# v1.net
KiCad netlist of a schematic drawn in EAGLE
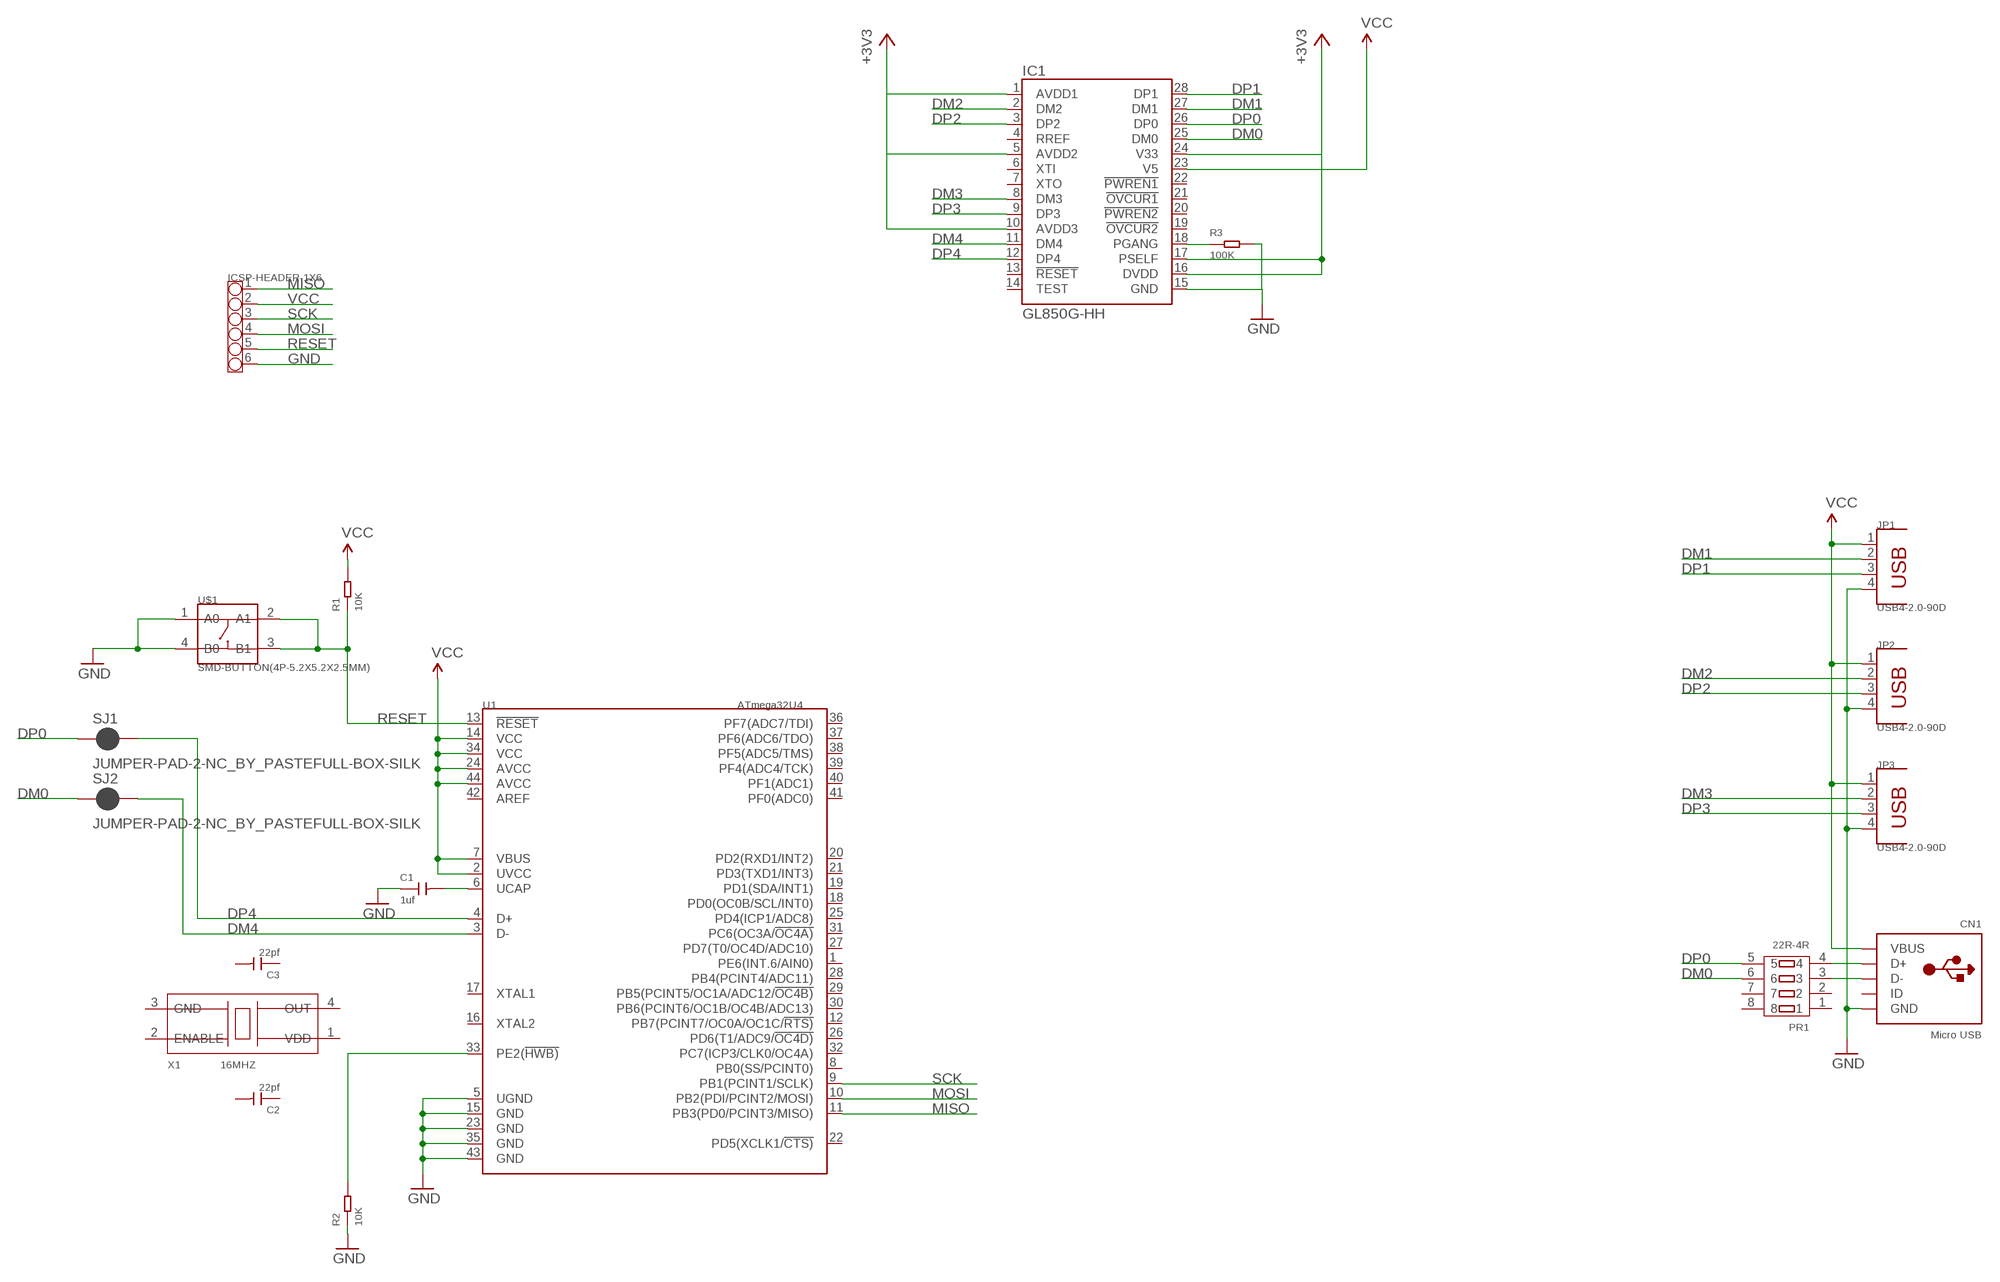
[diagram p0: schematic, sheet 1]

(export (version "E")
  (design (tool "Eeschema 10.0.6"))
  (components
    (comp (ref "C1")
      (value "1uf")
      (footprint "eagle-import:C0603")
      (fields (field (name "MPN") "CC0603KRX7R8BB105"))
      (libsource (lib "eagle-import") (part "CERAMIC-1UF-25V-10%-X7R(0603)"))
    )
    (comp (ref "C2")
      (value "22pf")
      (footprint "eagle-import:C0402")
      (fields (field (name "MPN") "CC0402JRNPO9BN220"))
      (libsource (lib "eagle-import") (part "CERAMIC-22PF-50V-5%-NPO(0402)"))
    )
    (comp (ref "C3")
      (value "22pf")
      (footprint "eagle-import:C0402")
      (fields (field (name "MPN") "CC0402JRNPO9BN220"))
      (libsource (lib "eagle-import") (part "CERAMIC-22PF-50V-5%-NPO(0402)"))
    )
    (comp (ref "CN1")
      (value "Micro USB")
      (footprint "eagle-import:USB-MINIB")
      (libsource (lib "eagle-import") (part "USBMINIB"))
    )
    (comp (ref "IC1")
      (value "GL850G-HH")
      (footprint "eagle-import:SSOP28")
      (libsource (lib "eagle-import") (part "GL850G-HH"))
    )
    (comp (ref "ICSP-HEADER-1X6")
      (value "CONNECTOR-HEADER-6P-3460650P1")
      (footprint "eagle-import:1X6P-2.54-2.54-11.6-3.0-BLACK-MALE")
      (libsource (lib "eagle-import") (part "CONNECTOR-HEADER-6P-3460650P1"))
    )
    (comp (ref "JP1")
      (value "USB4-2.0-90D")
      (footprint "eagle-import:USB4+2P-2.0-90D")
      (libsource (lib "eagle-import") (part "DIP-USB-A-TYPE-FMAL(4+2P-2.0-90D)"))
    )
    (comp (ref "JP2")
      (value "USB4-2.0-90D")
      (footprint "eagle-import:USB4+2P-2.0-90D")
      (libsource (lib "eagle-import") (part "DIP-USB-A-TYPE-FMAL(4+2P-2.0-90D)"))
    )
    (comp (ref "JP3")
      (value "USB4-2.0-90D")
      (footprint "eagle-import:USB4+2P-2.0-90D")
      (libsource (lib "eagle-import") (part "DIP-USB-A-TYPE-FMAL(4+2P-2.0-90D)"))
    )
    (comp (ref "PR1")
      (value "22R-4R")
      (footprint "eagle-import:RA1206-8")
      (fields (field (name "MPN") "YC324-JK-0722RL"))
      (libsource (lib "eagle-import") (part "SMD-RES-ARRAY-22R-4R(1206-8)"))
    )
    (comp (ref "R1")
      (value "10K")
      (footprint "eagle-import:R0603")
      (fields (field (name "MPN") "RC0603FR-0710KL"))
      (libsource (lib "eagle-import") (part "SMD-RES-10K-1%-1/10W(0603)"))
    )
    (comp (ref "R2")
      (value "10K")
      (footprint "eagle-import:R0603")
      (fields (field (name "MPN") "RC0603FR-0710KL"))
      (libsource (lib "eagle-import") (part "SMD-RES-10K-1%-1/10W(0603)"))
    )
    (comp (ref "R3")
      (value "100K")
      (footprint "eagle-import:R0805")
      (fields (field (name "MPN") "RC0805FR-07100KL"))
      (libsource (lib "eagle-import") (part "SMD-RES-100K-1%-1/8W(0805)"))
    )
    (comp (ref "SJ1")
      (value "JUMPER-PAD-2-NC_BY_PASTEFULL-BOX-SILK")
      (footprint "eagle-import:PAD-JUMPER-2-NC_BY_PASTE_YES_SILK_FULL_BOX")
      (libsource (lib "eagle-import") (part "JUMPER-PAD-2-NC_BY_PASTEFULL-BOX-SILK"))
    )
    (comp (ref "SJ2")
      (value "JUMPER-PAD-2-NC_BY_PASTEFULL-BOX-SILK")
      (footprint "eagle-import:PAD-JUMPER-2-NC_BY_PASTE_YES_SILK_FULL_BOX")
      (libsource (lib "eagle-import") (part "JUMPER-PAD-2-NC_BY_PASTEFULL-BOX-SILK"))
    )
    (comp (ref "U$1")
      (value "SMD-BUTTON(4P-5.2X5.2X2.5MM)")
      (footprint "eagle-import:SW4-SMD-5.2X5.2X2.5MM")
      (libsource (lib "eagle-import") (part "SMD-BUTTON(4P-5.2X5.2X2.5MM)"))
    )
    (comp (ref "U1")
      (value "ATmega32U4")
      (footprint "eagle-import:TQFP-44")
      (libsource (lib "eagle-import") (part "MCU-ATMEGA32U4-310010010"))
    )
    (comp (ref "X1")
      (value "16MHZ")
      (footprint "eagle-import:X4-SMD-3.2X2.5X0.7MM")
      (libsource (lib "eagle-import") (part "SMD-CRYSTAL-16MHZ-9PF-10PPM-60R(4P-3.2X2.5MM)"))
    )
  )
  (nets
    (net (code "1") (name "+3V3") (class "Default")
      (node (ref "IC1") (pin "1") (pinfunction "AVDD1_1") (pintype "power_in"))
      (node (ref "IC1") (pin "10") (pinfunction "AVDD3_10") (pintype "power_in"))
      (node (ref "IC1") (pin "16") (pinfunction "DVDD_16") (pintype "power_in"))
      (node (ref "IC1") (pin "17") (pinfunction "PSELF_17") (pintype "input"))
      (node (ref "IC1") (pin "24") (pinfunction "V33_24") (pintype "output"))
      (node (ref "IC1") (pin "5") (pinfunction "AVDD2_5") (pintype "power_in"))
    )
    (net (code "2") (name "/DM0") (class "Default")
      (node (ref "IC1") (pin "25") (pinfunction "DM0_25") (pintype "bidirectional"))
      (node (ref "PR1") (pin "6") (pinfunction "6_6") (pintype "bidirectional"))
      (node (ref "SJ2") (pin "1") (pinfunction "1_1") (pintype "passive"))
    )
    (net (code "3") (name "/DM1") (class "Default")
      (node (ref "IC1") (pin "27") (pinfunction "DM1_27") (pintype "bidirectional"))
      (node (ref "JP1") (pin "2") (pinfunction "2_2") (pintype "bidirectional"))
    )
    (net (code "4") (name "/DM2") (class "Default")
      (node (ref "IC1") (pin "2") (pinfunction "DM2_2") (pintype "bidirectional"))
      (node (ref "JP2") (pin "2") (pinfunction "2_2") (pintype "bidirectional"))
    )
    (net (code "5") (name "/DM3") (class "Default")
      (node (ref "IC1") (pin "8") (pinfunction "DM3_8") (pintype "bidirectional"))
      (node (ref "JP3") (pin "2") (pinfunction "2_2") (pintype "bidirectional"))
    )
    (net (code "6") (name "/DM4") (class "Default")
      (node (ref "IC1") (pin "11") (pinfunction "DM4_11") (pintype "bidirectional"))
      (node (ref "SJ2") (pin "2") (pinfunction "2_2") (pintype "passive"))
      (node (ref "U1") (pin "3") (pinfunction "D-_3") (pintype "bidirectional"))
    )
    (net (code "7") (name "/DP0") (class "Default")
      (node (ref "IC1") (pin "26") (pinfunction "DP0_26") (pintype "bidirectional"))
      (node (ref "PR1") (pin "5") (pinfunction "5_5") (pintype "bidirectional"))
      (node (ref "SJ1") (pin "1") (pinfunction "1_1") (pintype "passive"))
    )
    (net (code "8") (name "/DP1") (class "Default")
      (node (ref "IC1") (pin "28") (pinfunction "DP1_28") (pintype "bidirectional"))
      (node (ref "JP1") (pin "3") (pinfunction "3_3") (pintype "bidirectional"))
    )
    (net (code "9") (name "/DP2") (class "Default")
      (node (ref "IC1") (pin "3") (pinfunction "DP2_3") (pintype "bidirectional"))
      (node (ref "JP2") (pin "3") (pinfunction "3_3") (pintype "bidirectional"))
    )
    (net (code "10") (name "/DP3") (class "Default")
      (node (ref "IC1") (pin "9") (pinfunction "DP3_9") (pintype "bidirectional"))
      (node (ref "JP3") (pin "3") (pinfunction "3_3") (pintype "bidirectional"))
    )
    (net (code "11") (name "/DP4") (class "Default")
      (node (ref "IC1") (pin "12") (pinfunction "DP4_12") (pintype "bidirectional"))
      (node (ref "SJ1") (pin "2") (pinfunction "2_2") (pintype "passive"))
      (node (ref "U1") (pin "4") (pinfunction "D+_4") (pintype "bidirectional"))
    )
    (net (code "12") (name "/MISO") (class "Default")
      (node (ref "ICSP-HEADER-1X6") (pin "1") (pinfunction "1_1") (pintype "bidirectional"))
      (node (ref "U1") (pin "11") (pinfunction "PB3(PD0/PCINT3/MISO)_11") (pintype "bidirectional"))
    )
    (net (code "13") (name "/MOSI") (class "Default")
      (node (ref "ICSP-HEADER-1X6") (pin "4") (pinfunction "4_4") (pintype "bidirectional"))
      (node (ref "U1") (pin "10") (pinfunction "PB2(PDI/PCINT2/MOSI)_10") (pintype "bidirectional"))
    )
    (net (code "14") (name "/RESET") (class "Default")
      (node (ref "ICSP-HEADER-1X6") (pin "5") (pinfunction "5_5") (pintype "bidirectional"))
      (node (ref "R1") (pin "1") (pinfunction "1_1") (pintype "passive"))
      (node (ref "U$1") (pin "2") (pinfunction "A1_2") (pintype "bidirectional"))
      (node (ref "U$1") (pin "3") (pinfunction "B1_3") (pintype "bidirectional"))
      (node (ref "U1") (pin "13") (pinfunction "~{RESET}_13") (pintype "bidirectional"))
    )
    (net (code "15") (name "/SCK") (class "Default")
      (node (ref "ICSP-HEADER-1X6") (pin "3") (pinfunction "3_3") (pintype "bidirectional"))
      (node (ref "U1") (pin "9") (pinfunction "PB1(PCINT1/SCLK)_9") (pintype "bidirectional"))
    )
    (net (code "16") (name "GND") (class "Default")
      (node (ref "C1") (pin "1") (pinfunction "1_1") (pintype "passive"))
      (node (ref "CN1") (pin "GND") (pinfunction "GND_GND") (pintype "power_in"))
      (node (ref "IC1") (pin "15") (pinfunction "GND_15") (pintype "power_in"))
      (node (ref "ICSP-HEADER-1X6") (pin "6") (pinfunction "6_6") (pintype "bidirectional"))
      (node (ref "JP1") (pin "4") (pinfunction "4_4") (pintype "bidirectional"))
      (node (ref "JP2") (pin "4") (pinfunction "4_4") (pintype "bidirectional"))
      (node (ref "JP3") (pin "4") (pinfunction "4_4") (pintype "bidirectional"))
      (node (ref "R2") (pin "1") (pinfunction "1_1") (pintype "passive"))
      (node (ref "R3") (pin "2") (pinfunction "2_2") (pintype "passive"))
      (node (ref "U$1") (pin "1") (pinfunction "A0_1") (pintype "bidirectional"))
      (node (ref "U$1") (pin "4") (pinfunction "B0_4") (pintype "bidirectional"))
      (node (ref "U1") (pin "15") (pinfunction "GND_15") (pintype "bidirectional"))
      (node (ref "U1") (pin "23") (pinfunction "GND_23") (pintype "bidirectional"))
      (node (ref "U1") (pin "35") (pinfunction "GND_35") (pintype "bidirectional"))
      (node (ref "U1") (pin "43") (pinfunction "GND_43") (pintype "bidirectional"))
      (node (ref "U1") (pin "5") (pinfunction "UGND_5") (pintype "bidirectional"))
    )
    (net (code "17") (name "Net-(CN1-PadD+)") (class "Default")
      (node (ref "CN1") (pin "D+") (pinfunction "D+_D+") (pintype "bidirectional"))
      (node (ref "PR1") (pin "4") (pinfunction "4_4") (pintype "bidirectional"))
    )
    (net (code "18") (name "Net-(CN1-PadD-)") (class "Default")
      (node (ref "CN1") (pin "D-") (pinfunction "D-_D-") (pintype "bidirectional"))
      (node (ref "PR1") (pin "3") (pinfunction "3_3") (pintype "bidirectional"))
    )
    (net (code "19") (name "Net-(IC1-PGANG)") (class "Default")
      (node (ref "IC1") (pin "18") (pinfunction "PGANG_18") (pintype "bidirectional"))
      (node (ref "R3") (pin "1") (pinfunction "1_1") (pintype "passive"))
    )
    (net (code "20") (name "Net-(U1-PE2(~{HWB}))") (class "Default")
      (node (ref "R2") (pin "2") (pinfunction "2_2") (pintype "passive"))
      (node (ref "U1") (pin "33") (pinfunction "PE2(~{HWB})_33") (pintype "bidirectional"))
    )
    (net (code "21") (name "Net-(U1-UCAP)") (class "Default")
      (node (ref "C1") (pin "2") (pinfunction "2_2") (pintype "passive"))
      (node (ref "U1") (pin "6") (pinfunction "UCAP_6") (pintype "bidirectional"))
    )
    (net (code "22") (name "VCC") (class "Default")
      (node (ref "CN1") (pin "VBUS") (pinfunction "VBUS_VBUS") (pintype "power_in"))
      (node (ref "IC1") (pin "23") (pinfunction "V5_23") (pintype "power_in"))
      (node (ref "ICSP-HEADER-1X6") (pin "2") (pinfunction "2_2") (pintype "bidirectional"))
      (node (ref "JP1") (pin "1") (pinfunction "1_1") (pintype "bidirectional"))
      (node (ref "JP2") (pin "1") (pinfunction "1_1") (pintype "bidirectional"))
      (node (ref "JP3") (pin "1") (pinfunction "1_1") (pintype "bidirectional"))
      (node (ref "R1") (pin "2") (pinfunction "2_2") (pintype "passive"))
      (node (ref "U1") (pin "14") (pinfunction "VCC_14") (pintype "bidirectional"))
      (node (ref "U1") (pin "2") (pinfunction "UVCC_2") (pintype "bidirectional"))
      (node (ref "U1") (pin "24") (pinfunction "AVCC_24") (pintype "bidirectional"))
      (node (ref "U1") (pin "34") (pinfunction "VCC_34") (pintype "bidirectional"))
      (node (ref "U1") (pin "44") (pinfunction "AVCC_44") (pintype "bidirectional"))
      (node (ref "U1") (pin "7") (pinfunction "VBUS_7") (pintype "bidirectional"))
    )
    (net (code "23") (name "unconnected-(C2-Pad1)") (class "Default")
      (node (ref "C2") (pin "1") (pinfunction "1_1") (pintype "passive"))
    )
    (net (code "24") (name "unconnected-(C2-Pad2)") (class "Default")
      (node (ref "C2") (pin "2") (pinfunction "2_2") (pintype "passive"))
    )
    (net (code "25") (name "unconnected-(C3-Pad1)") (class "Default")
      (node (ref "C3") (pin "1") (pinfunction "1_1") (pintype "passive"))
    )
    (net (code "26") (name "unconnected-(C3-Pad2)") (class "Default")
      (node (ref "C3") (pin "2") (pinfunction "2_2") (pintype "passive"))
    )
    (net (code "27") (name "unconnected-(CN1-PadID)") (class "Default")
      (node (ref "CN1") (pin "ID") (pinfunction "ID_ID") (pintype "bidirectional"))
    )
    (net (code "28") (name "unconnected-(IC1-RREF-Pad4)") (class "Default")
      (node (ref "IC1") (pin "4") (pinfunction "RREF_4") (pintype "bidirectional"))
    )
    (net (code "29") (name "unconnected-(IC1-TEST-Pad14)") (class "Default")
      (node (ref "IC1") (pin "14") (pinfunction "TEST_14") (pintype "input"))
    )
    (net (code "30") (name "unconnected-(IC1-XTI-Pad6)") (class "Default")
      (node (ref "IC1") (pin "6") (pinfunction "XTI_6") (pintype "input"))
    )
    (net (code "31") (name "unconnected-(IC1-XTO-Pad7)") (class "Default")
      (node (ref "IC1") (pin "7") (pinfunction "XTO_7") (pintype "output"))
    )
    (net (code "32") (name "unconnected-(IC1-~{OVCUR1}-Pad21)") (class "Default")
      (node (ref "IC1") (pin "21") (pinfunction "~{OVCUR1}_21") (pintype "input"))
    )
    (net (code "33") (name "unconnected-(IC1-~{OVCUR2}-Pad19)") (class "Default")
      (node (ref "IC1") (pin "19") (pinfunction "~{OVCUR2}_19") (pintype "input"))
    )
    (net (code "34") (name "unconnected-(IC1-~{PWREN1}-Pad22)") (class "Default")
      (node (ref "IC1") (pin "22") (pinfunction "~{PWREN1}_22") (pintype "output"))
    )
    (net (code "35") (name "unconnected-(IC1-~{PWREN2}-Pad20)") (class "Default")
      (node (ref "IC1") (pin "20") (pinfunction "~{PWREN2}_20") (pintype "output"))
    )
    (net (code "36") (name "unconnected-(IC1-~{RESET}-Pad13)") (class "Default")
      (node (ref "IC1") (pin "13") (pinfunction "~{RESET}_13") (pintype "input"))
    )
    (net (code "37") (name "unconnected-(PR1-Pad1)") (class "Default")
      (node (ref "PR1") (pin "1") (pinfunction "1_1") (pintype "bidirectional"))
    )
    (net (code "38") (name "unconnected-(PR1-Pad2)") (class "Default")
      (node (ref "PR1") (pin "2") (pinfunction "2_2") (pintype "bidirectional"))
    )
    (net (code "39") (name "unconnected-(PR1-Pad7)") (class "Default")
      (node (ref "PR1") (pin "7") (pinfunction "7_7") (pintype "bidirectional"))
    )
    (net (code "40") (name "unconnected-(PR1-Pad8)") (class "Default")
      (node (ref "PR1") (pin "8") (pinfunction "8_8") (pintype "bidirectional"))
    )
    (net (code "41") (name "unconnected-(U1-AREF-Pad42)") (class "Default")
      (node (ref "U1") (pin "42") (pinfunction "AREF_42") (pintype "bidirectional"))
    )
    (net (code "42") (name "unconnected-(U1-PB0(SS{slash}PCINT0)-Pad8)") (class "Default")
      (node (ref "U1") (pin "8") (pinfunction "PB0(SS/PCINT0)_8") (pintype "bidirectional"))
    )
    (net (code "43") (name "unconnected-(U1-PB4(PCINT4{slash}ADC11)-Pad28)") (class "Default")
      (node (ref "U1") (pin "28") (pinfunction "PB4(PCINT4/ADC11)_28") (pintype "bidirectional"))
    )
    (net (code "44") (name "unconnected-(U1-PB5(PCINT5{slash}OC1A{slash}ADC12{slash}~{OC4B})-Pad29)") (class "Default")
      (node (ref "U1") (pin "29") (pinfunction "PB5(PCINT5/OC1A/ADC12/~{OC4B})_29") (pintype "bidirectional"))
    )
    (net (code "45") (name "unconnected-(U1-PB6(PCINT6{slash}OC1B{slash}OC4B{slash}ADC13)-Pad30)") (class "Default")
      (node (ref "U1") (pin "30") (pinfunction "PB6(PCINT6/OC1B/OC4B/ADC13)_30") (pintype "bidirectional"))
    )
    (net (code "46") (name "unconnected-(U1-PB7(PCINT7{slash}OC0A{slash}OC1C{slash}~{RTS})-Pad12)") (class "Default")
      (node (ref "U1") (pin "12") (pinfunction "PB7(PCINT7/OC0A/OC1C/~{RTS})_12") (pintype "bidirectional"))
    )
    (net (code "47") (name "unconnected-(U1-PC6(OC3A{slash}~{OC4A})-Pad31)") (class "Default")
      (node (ref "U1") (pin "31") (pinfunction "PC6(OC3A/~{OC4A})_31") (pintype "bidirectional"))
    )
    (net (code "48") (name "unconnected-(U1-PC7(ICP3{slash}CLK0{slash}OC4A)-Pad32)") (class "Default")
      (node (ref "U1") (pin "32") (pinfunction "PC7(ICP3/CLK0/OC4A)_32") (pintype "bidirectional"))
    )
    (net (code "49") (name "unconnected-(U1-PD0(OC0B{slash}SCL{slash}INT0)-Pad18)") (class "Default")
      (node (ref "U1") (pin "18") (pinfunction "PD0(OC0B/SCL/INT0)_18") (pintype "bidirectional"))
    )
    (net (code "50") (name "unconnected-(U1-PD1(SDA{slash}INT1)-Pad19)") (class "Default")
      (node (ref "U1") (pin "19") (pinfunction "PD1(SDA/INT1)_19") (pintype "bidirectional"))
    )
    (net (code "51") (name "unconnected-(U1-PD2(RXD1{slash}INT2)-Pad20)") (class "Default")
      (node (ref "U1") (pin "20") (pinfunction "PD2(RXD1/INT2)_20") (pintype "bidirectional"))
    )
    (net (code "52") (name "unconnected-(U1-PD3(TXD1{slash}INT3)-Pad21)") (class "Default")
      (node (ref "U1") (pin "21") (pinfunction "PD3(TXD1/INT3)_21") (pintype "bidirectional"))
    )
    (net (code "53") (name "unconnected-(U1-PD4(ICP1{slash}ADC8)-Pad25)") (class "Default")
      (node (ref "U1") (pin "25") (pinfunction "PD4(ICP1/ADC8)_25") (pintype "bidirectional"))
    )
    (net (code "54") (name "unconnected-(U1-PD5(XCLK1{slash}~{CTS})-Pad22)") (class "Default")
      (node (ref "U1") (pin "22") (pinfunction "PD5(XCLK1/~{CTS})_22") (pintype "bidirectional"))
    )
    (net (code "55") (name "unconnected-(U1-PD6(T1{slash}ADC9{slash}~{OC4D})-Pad26)") (class "Default")
      (node (ref "U1") (pin "26") (pinfunction "PD6(T1/ADC9/~{OC4D})_26") (pintype "bidirectional"))
    )
    (net (code "56") (name "unconnected-(U1-PD7(T0{slash}OC4D{slash}ADC10)-Pad27)") (class "Default")
      (node (ref "U1") (pin "27") (pinfunction "PD7(T0/OC4D/ADC10)_27") (pintype "bidirectional"))
    )
    (net (code "57") (name "unconnected-(U1-PE6(INT.6{slash}AIN0)-Pad1)") (class "Default")
      (node (ref "U1") (pin "1") (pinfunction "PE6(INT.6/AIN0)_1") (pintype "bidirectional"))
    )
    (net (code "58") (name "unconnected-(U1-PF0(ADC0)-Pad41)") (class "Default")
      (node (ref "U1") (pin "41") (pinfunction "PF0(ADC0)_41") (pintype "bidirectional"))
    )
    (net (code "59") (name "unconnected-(U1-PF1(ADC1)-Pad40)") (class "Default")
      (node (ref "U1") (pin "40") (pinfunction "PF1(ADC1)_40") (pintype "bidirectional"))
    )
    (net (code "60") (name "unconnected-(U1-PF4(ADC4{slash}TCK)-Pad39)") (class "Default")
      (node (ref "U1") (pin "39") (pinfunction "PF4(ADC4/TCK)_39") (pintype "bidirectional"))
    )
    (net (code "61") (name "unconnected-(U1-PF5(ADC5{slash}TMS)-Pad38)") (class "Default")
      (node (ref "U1") (pin "38") (pinfunction "PF5(ADC5/TMS)_38") (pintype "bidirectional"))
    )
    (net (code "62") (name "unconnected-(U1-PF6(ADC6{slash}TDO)-Pad37)") (class "Default")
      (node (ref "U1") (pin "37") (pinfunction "PF6(ADC6/TDO)_37") (pintype "bidirectional"))
    )
    (net (code "63") (name "unconnected-(U1-PF7(ADC7{slash}TDI)-Pad36)") (class "Default")
      (node (ref "U1") (pin "36") (pinfunction "PF7(ADC7/TDI)_36") (pintype "bidirectional"))
    )
    (net (code "64") (name "unconnected-(U1-XTAL1-Pad17)") (class "Default")
      (node (ref "U1") (pin "17") (pinfunction "XTAL1_17") (pintype "bidirectional"))
    )
    (net (code "65") (name "unconnected-(U1-XTAL2-Pad16)") (class "Default")
      (node (ref "U1") (pin "16") (pinfunction "XTAL2_16") (pintype "bidirectional"))
    )
    (net (code "66") (name "unconnected-(X1-ENABLE-Pad2)") (class "Default")
      (node (ref "X1") (pin "2") (pinfunction "ENABLE_2") (pintype "bidirectional"))
    )
    (net (code "67") (name "unconnected-(X1-GND-Pad3)") (class "Default")
      (node (ref "X1") (pin "3") (pinfunction "GND_3") (pintype "bidirectional"))
    )
    (net (code "68") (name "unconnected-(X1-OUT-Pad4)") (class "Default")
      (node (ref "X1") (pin "4") (pinfunction "OUT_4") (pintype "bidirectional"))
    )
    (net (code "69") (name "unconnected-(X1-VDD-Pad1)") (class "Default")
      (node (ref "X1") (pin "1") (pinfunction "VDD_1") (pintype "bidirectional"))
    )
  )
)
